# rfm_dil_adapter.net
KiCad netlist of a schematic drawn in EAGLE
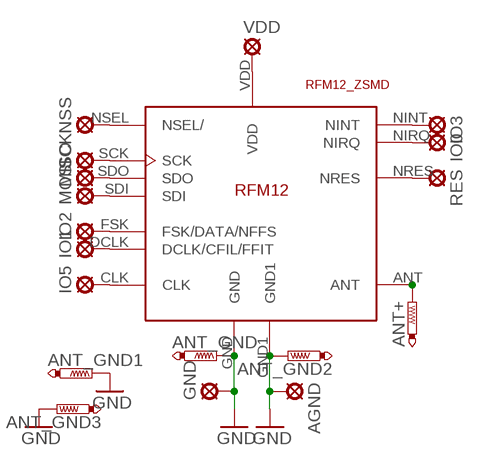
[diagram p0: schematic, sheet 1]

(export (version "E")
  (design (tool "Eeschema 10.0.6"))
  (components
    (comp (ref "AGND")
      (value "LSP10")
      (footprint "eagle-import:LSP10")
      (libsource (lib "eagle-import") (part "LSP10"))
    )
    (comp (ref "ANT+")
      (value "PTR1TP20SQ")
      (footprint "eagle-import:TP20SQ")
      (libsource (lib "eagle-import") (part "PTR1TP20SQ"))
    )
    (comp (ref "ANT_GND")
      (value "PTR1TP20SQ")
      (footprint "eagle-import:TP20SQ")
      (libsource (lib "eagle-import") (part "PTR1TP20SQ"))
    )
    (comp (ref "ANT_GND1")
      (value "PTR1TP20SQ")
      (footprint "eagle-import:TP20SQ")
      (libsource (lib "eagle-import") (part "PTR1TP20SQ"))
    )
    (comp (ref "ANT_GND2")
      (value "PTR1TP20SQ")
      (footprint "eagle-import:TP20SQ")
      (libsource (lib "eagle-import") (part "PTR1TP20SQ"))
    )
    (comp (ref "ANT_GND3")
      (value "PTR1TP20SQ")
      (footprint "eagle-import:TP20SQ")
      (libsource (lib "eagle-import") (part "PTR1TP20SQ"))
    )
    (comp (ref "GND")
      (value "LSP10")
      (footprint "eagle-import:LSP10")
      (libsource (lib "eagle-import") (part "LSP10"))
    )
    (comp (ref "IO0")
      (value "LSP10")
      (footprint "eagle-import:LSP10")
      (libsource (lib "eagle-import") (part "LSP10"))
    )
    (comp (ref "IO1")
      (value "LSP10")
      (footprint "eagle-import:LSP10")
      (libsource (lib "eagle-import") (part "LSP10"))
    )
    (comp (ref "IO2")
      (value "LSP10")
      (footprint "eagle-import:LSP10")
      (libsource (lib "eagle-import") (part "LSP10"))
    )
    (comp (ref "IO3")
      (value "LSP10")
      (footprint "eagle-import:LSP10")
      (libsource (lib "eagle-import") (part "LSP10"))
    )
    (comp (ref "IO5")
      (value "LSP10")
      (footprint "eagle-import:LSP10")
      (libsource (lib "eagle-import") (part "LSP10"))
    )
    (comp (ref "MISO")
      (value "LSP10")
      (footprint "eagle-import:LSP10")
      (libsource (lib "eagle-import") (part "LSP10"))
    )
    (comp (ref "MOSI")
      (value "LSP10")
      (footprint "eagle-import:LSP10")
      (libsource (lib "eagle-import") (part "LSP10"))
    )
    (comp (ref "NSS")
      (value "LSP10")
      (footprint "eagle-import:LSP10")
      (libsource (lib "eagle-import") (part "LSP10"))
    )
    (comp (ref "RES")
      (value "LSP10")
      (footprint "eagle-import:LSP10")
      (libsource (lib "eagle-import") (part "LSP10"))
    )
    (comp (ref "SCK")
      (value "LSP10")
      (footprint "eagle-import:LSP10")
      (libsource (lib "eagle-import") (part "LSP10"))
    )
    (comp (ref "U$1")
      (value "RFM12_ZSMD")
      (footprint "eagle-import:RFM12_Z")
      (libsource (lib "eagle-import") (part "RFM12_ZSMD"))
    )
    (comp (ref "VDD")
      (value "LSP10")
      (footprint "eagle-import:LSP10")
      (libsource (lib "eagle-import") (part "LSP10"))
    )
  )
  (nets
    (net (code "1") (name "GND") (class "Default")
      (node (ref "AGND") (pin "MP") (pinfunction "MP_MP") (pintype "passive"))
      (node (ref "ANT_GND") (pin "TP") (pinfunction "TP_TP") (pintype "input"))
      (node (ref "ANT_GND1") (pin "TP") (pinfunction "TP_TP") (pintype "input"))
      (node (ref "ANT_GND2") (pin "TP") (pinfunction "TP_TP") (pintype "input"))
      (node (ref "ANT_GND3") (pin "TP") (pinfunction "TP_TP") (pintype "input"))
      (node (ref "GND") (pin "MP") (pinfunction "MP_MP") (pintype "passive"))
      (node (ref "U$1") (pin "GND") (pinfunction "GND_GND") (pintype "passive"))
      (node (ref "U$1") (pin "GND1") (pinfunction "GND1_GND1") (pintype "passive"))
    )
    (net (code "2") (name "Net-(ANT+-PadTP)") (class "Default")
      (node (ref "ANT+") (pin "TP") (pinfunction "TP_TP") (pintype "input"))
      (node (ref "U$1") (pin "ANT") (pinfunction "ANT_ANT") (pintype "bidirectional"))
    )
    (net (code "3") (name "Net-(IO0-PadMP)") (class "Default")
      (node (ref "IO0") (pin "MP") (pinfunction "MP_MP") (pintype "passive"))
      (node (ref "U$1") (pin "NIRQ") (pinfunction "NIRQ_NIRQ") (pintype "output"))
    )
    (net (code "4") (name "Net-(IO3-PadMP)") (class "Default")
      (node (ref "IO3") (pin "MP") (pinfunction "MP_MP") (pintype "passive"))
      (node (ref "U$1") (pin "NINT") (pinfunction "NINT_NINT") (pintype "bidirectional"))
    )
    (net (code "5") (name "Net-(IO5-PadMP)") (class "Default")
      (node (ref "IO5") (pin "MP") (pinfunction "MP_MP") (pintype "passive"))
      (node (ref "U$1") (pin "CLK") (pinfunction "CLK_CLK") (pintype "output"))
    )
    (net (code "6") (name "Net-(MISO-PadMP)") (class "Default")
      (node (ref "MISO") (pin "MP") (pinfunction "MP_MP") (pintype "passive"))
      (node (ref "U$1") (pin "SDO") (pinfunction "SDO_SDO") (pintype "output"))
    )
    (net (code "7") (name "Net-(MOSI-PadMP)") (class "Default")
      (node (ref "MOSI") (pin "MP") (pinfunction "MP_MP") (pintype "passive"))
      (node (ref "U$1") (pin "SDI") (pinfunction "SDI_SDI") (pintype "input"))
    )
    (net (code "8") (name "Net-(RES-PadMP)") (class "Default")
      (node (ref "RES") (pin "MP") (pinfunction "MP_MP") (pintype "passive"))
      (node (ref "U$1") (pin "NRES") (pinfunction "NRES_NRES") (pintype "bidirectional"))
    )
    (net (code "9") (name "Net-(SCK-PadMP)") (class "Default")
      (node (ref "SCK") (pin "MP") (pinfunction "MP_MP") (pintype "passive"))
      (node (ref "U$1") (pin "SCK") (pinfunction "SCK_SCK") (pintype "input"))
    )
    (net (code "10") (name "Net-(U$1-DCLK{slash}CFIL{slash}FFIT)") (class "Default")
      (node (ref "IO1") (pin "MP") (pinfunction "MP_MP") (pintype "passive"))
      (node (ref "U$1") (pin "DCLK") (pinfunction "DCLK/CFIL/FFIT_DCLK") (pintype "bidirectional"))
    )
    (net (code "11") (name "Net-(U$1-FSK{slash}DATA{slash}NFFS)") (class "Default")
      (node (ref "IO2") (pin "MP") (pinfunction "MP_MP") (pintype "passive"))
      (node (ref "U$1") (pin "FSK") (pinfunction "FSK/DATA/NFFS_FSK") (pintype "bidirectional"))
    )
    (net (code "12") (name "Net-(U$1-NSEL{slash})") (class "Default")
      (node (ref "NSS") (pin "MP") (pinfunction "MP_MP") (pintype "passive"))
      (node (ref "U$1") (pin "NSEL") (pinfunction "NSEL/_NSEL") (pintype "input"))
    )
    (net (code "13") (name "Net-(U$1-PadVDD)") (class "Default")
      (node (ref "U$1") (pin "VDD") (pinfunction "VDD_VDD") (pintype "power_in"))
      (node (ref "VDD") (pin "MP") (pinfunction "MP_MP") (pintype "passive"))
    )
  )
)
